# Input-Output.net
KiCad netlist of a schematic drawn in Altium Designer
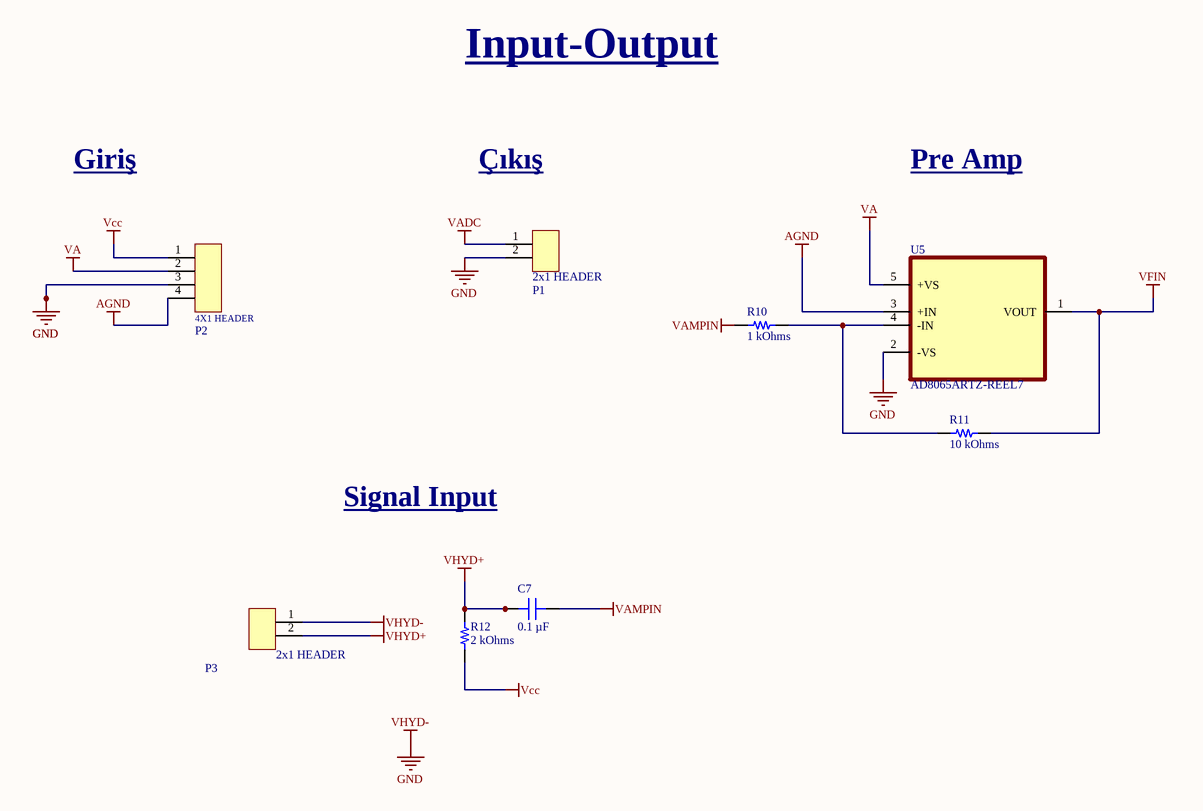
[diagram p0: Input-Output.SchDoc]

(export (version "E")
  (design (tool "Eeschema 10.0.6"))
  (components
    (comp (ref "C7")
      (value "0.1 µF")
      (footprint "RES 0805_2012")
      (description "CAP CER 0.1UF 50V X7R 0805")
      (fields (field (name "PART NUMBER") "CC0805MRX7R9BB104") (field (name "MANUFACTURER") "Yageo"))
      (libsource (lib "Celestial Altium Library - altium_library") (part "Capacitor"))
    )
    (comp (ref "P1")
      (value "WIRE-TO BOARD WAFER, 2.5MM, 2 CO")
      (footprint "51025-02-0100-01")
      (description "Connector Header Through Hole 2 position 0.098\" (2.50mm)")
      (fields
        (field (name "MANUFACTURER") "CNC Tech")
        (field (name "MANUFACTURER PART NUMBER") "51025-02-0100-01")
      )
      (libsource (lib "libv1") (part "51025-02-0100-01"))
    )
    (comp (ref "P2")
      (value "WIRE-TO BOARD HEADER, 2.5MM, 4 C")
      (footprint "51125-04-0200-01")
      (description "Wire-to Board Header, 2.5MM, 4 C")
      (fields
        (field (name "MANUFACTURER") "CNC Tech")
        (field (name "MANUFACTURER PART NUMBER") "51125-04-0200-01")
      )
      (libsource (lib "libv1") (part "51125-04-0200-01"))
    )
    (comp (ref "P3")
      (value "WIRE-TO BOARD WAFER, 2.5MM, 2 CO")
      (footprint "51025-02-0100-01")
      (description "Connector Header Through Hole 2 position 0.098\" (2.50mm)")
      (fields
        (field (name "MANUFACTURER") "CNC Tech")
        (field (name "MANUFACTURER PART NUMBER") "51025-02-0100-01")
      )
      (libsource (lib "") (part "51025-02-0100-01_1"))
    )
    (comp (ref "R10")
      (value "1 kOhms")
      (footprint "RES 1206_3216 RF")
      (description "RES SMD 1K OHM 5% 1/3W 0805")
      (fields
        (field (name "PART NUMBER") "CRGH0805J1K0")
        (field (name "MANUFACTURER") "TE Connectivity Passive Product")
      )
      (libsource (lib "Celestial Altium Library - altium_library") (part "Resistor"))
    )
    (comp (ref "R11")
      (value "10 kOhms")
      (footprint "RES 1206_3216 RF")
      (description "RES 10K OHM 0.5% 1/8W 0805")
      (fields
        (field (name "PART NUMBER") "RNCF0805DTE10K0")
        (field (name "MANUFACTURER") "Stackpole Electronics Inc")
      )
      (libsource (lib "Celestial Altium Library - altium_library") (part "Resistor"))
    )
    (comp (ref "R12")
      (value "2 kOhms")
      (footprint "RES 1206_3216 RF")
      (description "RES SMD 2K OHM 1% 0.4W 0805")
      (fields (field (name "PART NUMBER") "RCS08052K00FKEA") (field (name "MANUFACTURER") "Vishay Dale"))
      (libsource (lib "Celestial Altium Library - altium_library") (part "Resistor"))
    )
    (comp (ref "U5")
      (value "AD8065ARTZ-REEL7")
      (footprint "SOT95P290X145-5N")
      (description "Voltage Feedback Amplifier 1 Circuit Rail-to-Rail SOT-23-5")
      (fields (field (name "MF") "Analog Devices"))
      (libsource (lib "AD8065ARTZ-REEL7") (part "AD8065ARTZ-REEL7"))
    )
  )
  (nets
    (net (code "1") (name "AGND") (class "Default")
      (node (ref "P2") (pin "4") (pinfunction "6_4") (pintype "passive"))
      (node (ref "U5") (pin "3") (pinfunction "+IN_3") (pintype "passive"))
    )
    (net (code "2") (name "GND") (class "Default")
      (node (ref "P1") (pin "2") (pintype "passive"))
      (node (ref "P2") (pin "3") (pinfunction "7_3") (pintype "passive"))
      (node (ref "P3") (pin "1") (pintype "passive"))
      (node (ref "U5") (pin "2") (pinfunction "-VS_2") (pintype "power_in"))
    )
    (net (code "3") (name "Net-(U5--IN)") (class "Default")
      (node (ref "R10") (pin "2") (pinfunction "2_2") (pintype "passive"))
      (node (ref "R11") (pin "1") (pinfunction "1_1") (pintype "passive"))
      (node (ref "U5") (pin "4") (pinfunction "-IN_4") (pintype "passive"))
    )
    (net (code "4") (name "VA") (class "Default")
      (node (ref "P2") (pin "2") (pinfunction "8_2") (pintype "passive"))
      (node (ref "U5") (pin "5") (pinfunction "+VS_5") (pintype "power_in"))
    )
    (net (code "5") (name "VADC") (class "Default") (node (ref "P1") (pin "1") (pintype "passive")))
    (net (code "6") (name "VAMPIN") (class "Default")
      (node (ref "C7") (pin "2") (pinfunction "2_2") (pintype "passive"))
      (node (ref "R10") (pin "1") (pinfunction "1_1") (pintype "passive"))
    )
    (net (code "7") (name "VFIN") (class "Default")
      (node (ref "R11") (pin "2") (pinfunction "2_2") (pintype "passive"))
      (node (ref "U5") (pin "1") (pinfunction "VOUT_1") (pintype "passive"))
    )
    (net (code "8") (name "VHYD+") (class "Default")
      (node (ref "C7") (pin "1") (pinfunction "1_1") (pintype "passive"))
      (node (ref "P3") (pin "2") (pintype "passive"))
      (node (ref "R12") (pin "2") (pinfunction "2_2") (pintype "passive"))
    )
    (net (code "9") (name "Vcc") (class "Default")
      (node (ref "P2") (pin "1") (pintype "passive"))
      (node (ref "R12") (pin "1") (pinfunction "1_1") (pintype "passive"))
    )
  )
)
